# Main.net
KiCad netlist of a schematic drawn in EAGLE
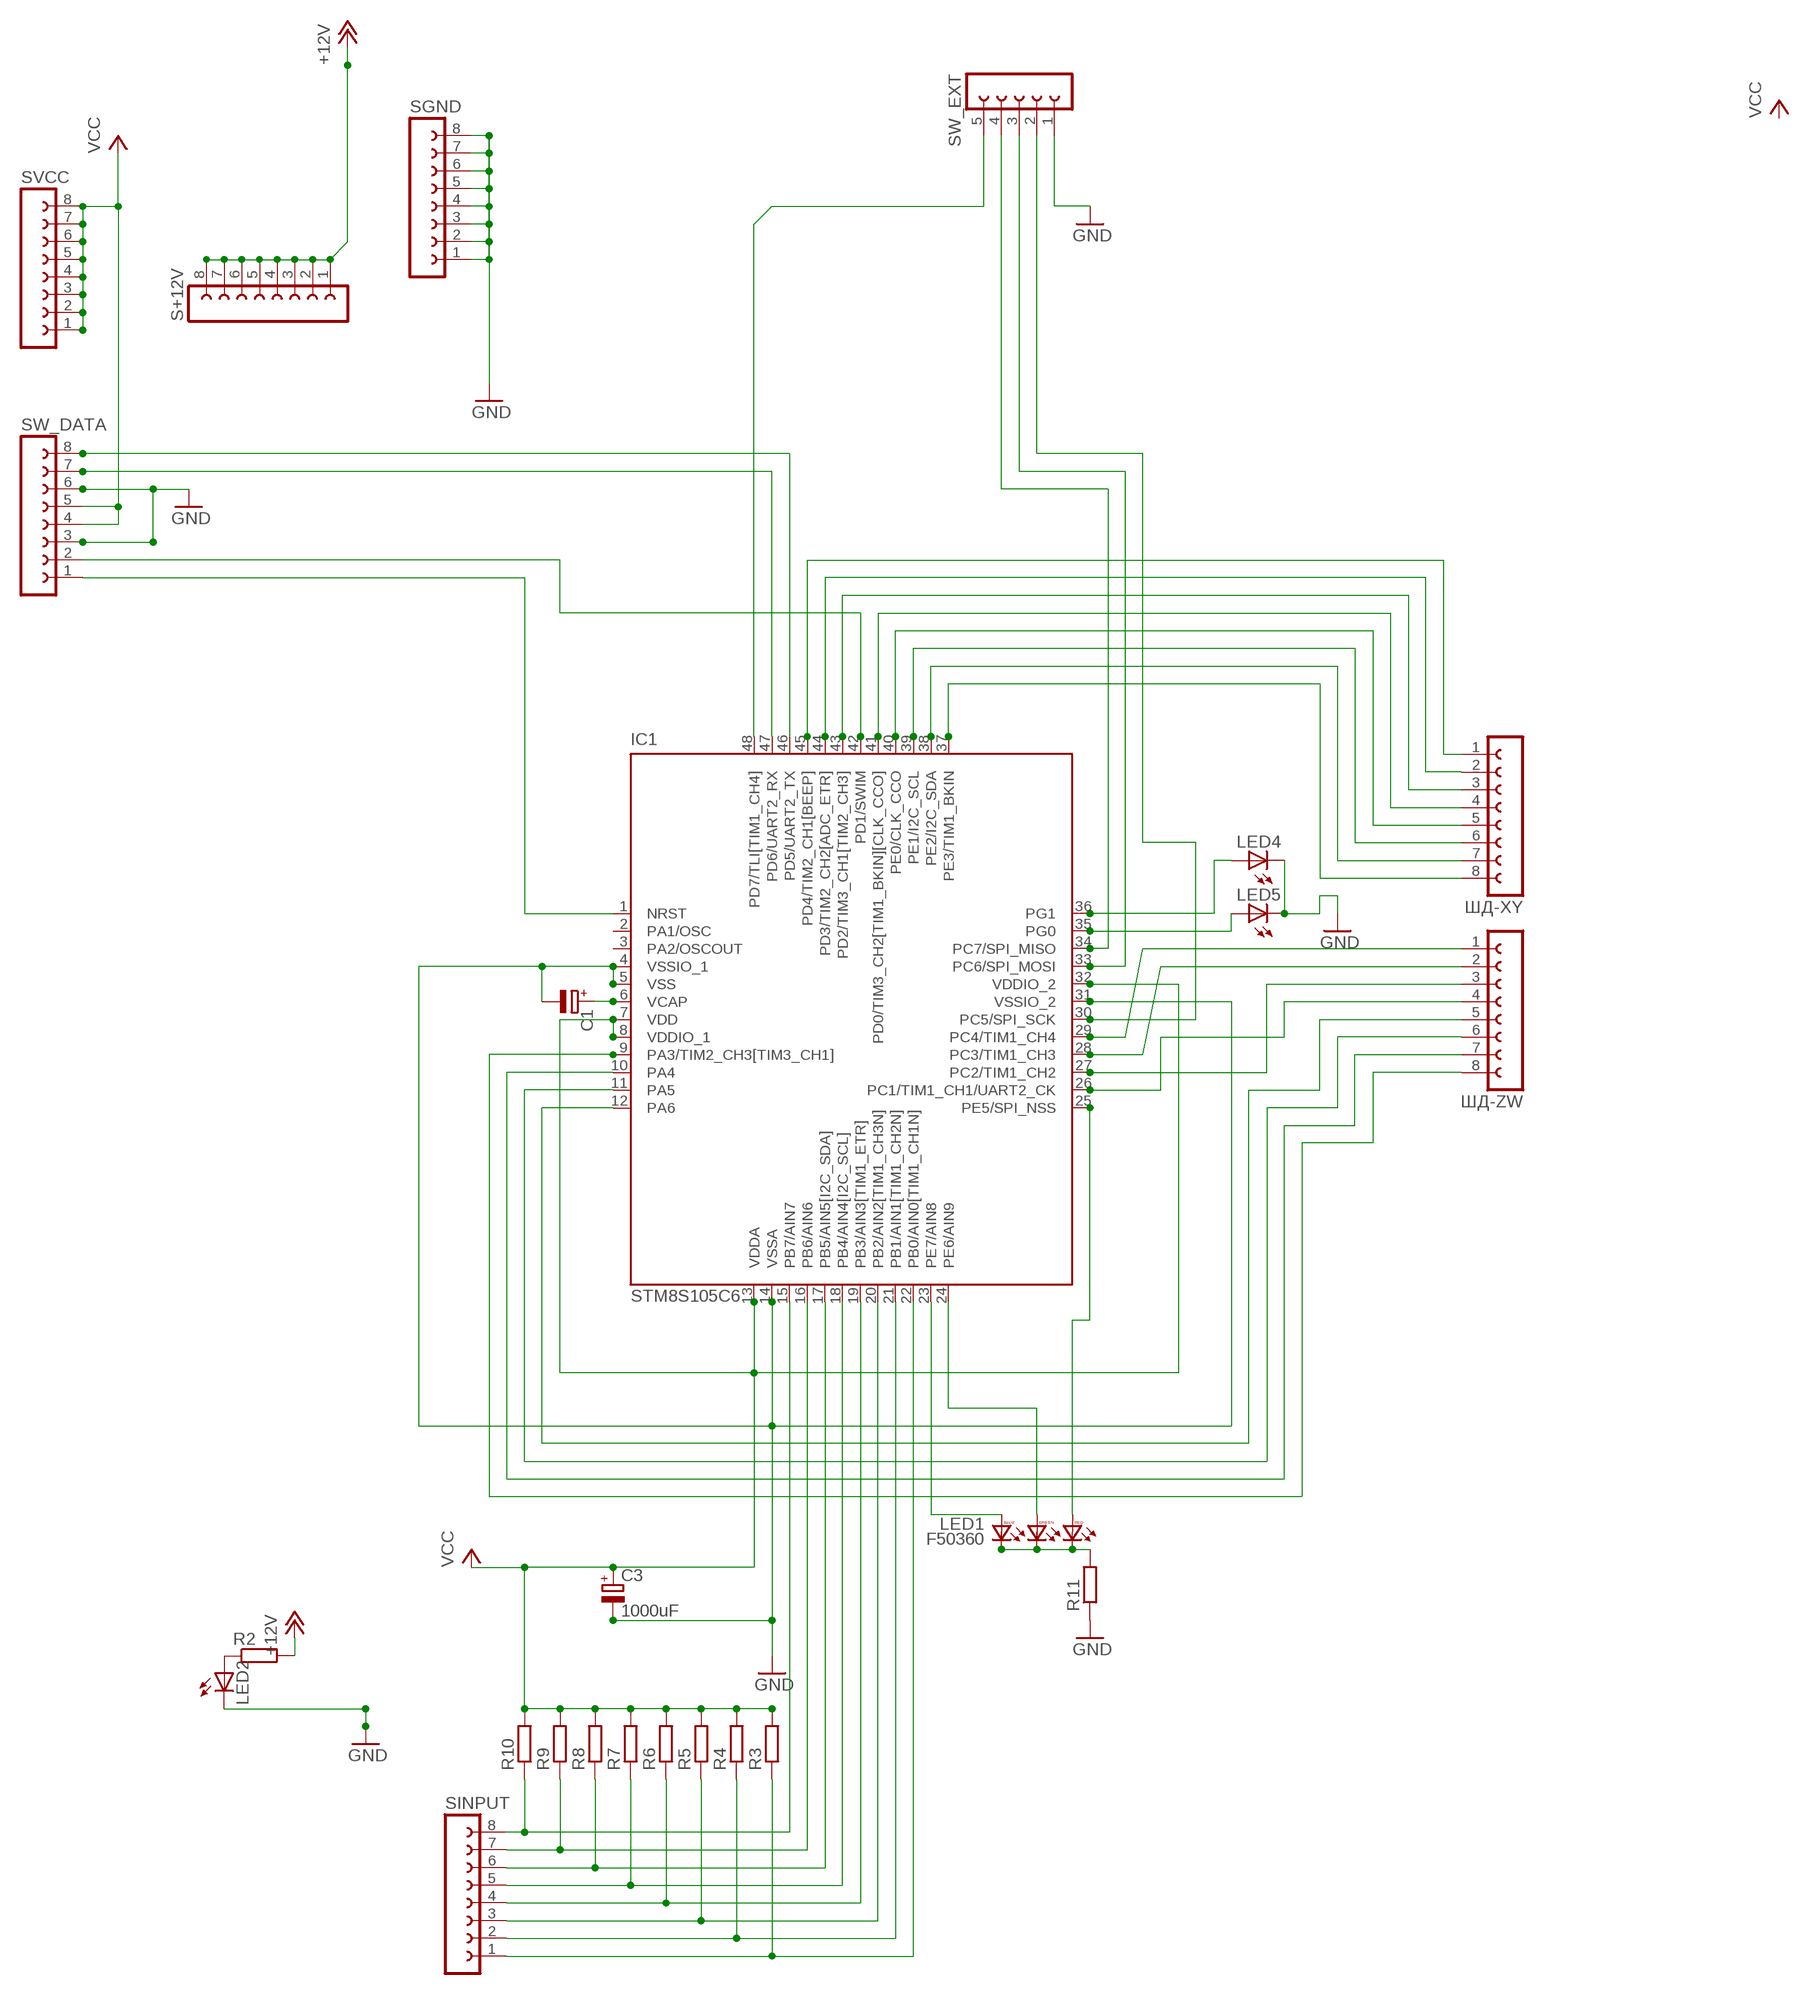
[diagram p0: schematic, sheet 1]

(export (version "E")
  (design (tool "Eeschema 10.0.6"))
  (components
    (comp (ref "C1")
      (value "CPOL-EUR/2012-12W")
      (footprint "eagle-import:R_2012-12W")
      (libsource (lib "eagle-import") (part "resistor_CPOL-EUR/2012-12W"))
    )
    (comp (ref "C3")
      (value "1000uF")
      (footprint "eagle-import:SANYO-OSCON_9E")
      (libsource (lib "eagle-import") (part "CPOL-EUSANYO_9E"))
    )
    (comp (ref "IC1")
      (value "STM8S105C6")
      (footprint "eagle-import:LQFP48-7X7")
      (fields (field (name "MPN") "STM8S105C6T6"))
      (libsource (lib "eagle-import") (part "STM8S105C6"))
    )
    (comp (ref "LED1")
      (value "F50360")
      (footprint "eagle-import:F50360")
      (libsource (lib "eagle-import") (part "F50360"))
    )
    (comp (ref "LED2")
      (value "LED3MM")
      (footprint "eagle-import:LED3MM")
      (libsource (lib "eagle-import") (part "LED3MM"))
    )
    (comp (ref "LED4")
      (value "LED3MM")
      (footprint "eagle-import:LED3MM")
      (libsource (lib "eagle-import") (part "LED3MM"))
    )
    (comp (ref "LED5")
      (value "LED3MM")
      (footprint "eagle-import:LED3MM")
      (libsource (lib "eagle-import") (part "LED3MM"))
    )
    (comp (ref "R2")
      (value "R-EU_0204/7")
      (footprint "eagle-import:0204_7")
      (libsource (lib "eagle-import") (part "R-EU_0204/7"))
    )
    (comp (ref "R3")
      (value "R-EU_M0805")
      (footprint "eagle-import:M0805")
      (libsource (lib "eagle-import") (part "R-EU_M0805"))
    )
    (comp (ref "R4")
      (value "R-EU_M0805")
      (footprint "eagle-import:M0805")
      (libsource (lib "eagle-import") (part "R-EU_M0805"))
    )
    (comp (ref "R5")
      (value "R-EU_M0805")
      (footprint "eagle-import:M0805")
      (libsource (lib "eagle-import") (part "R-EU_M0805"))
    )
    (comp (ref "R6")
      (value "R-EU_M0805")
      (footprint "eagle-import:M0805")
      (libsource (lib "eagle-import") (part "R-EU_M0805"))
    )
    (comp (ref "R7")
      (value "R-EU_M0805")
      (footprint "eagle-import:M0805")
      (libsource (lib "eagle-import") (part "R-EU_M0805"))
    )
    (comp (ref "R8")
      (value "R-EU_M0805")
      (footprint "eagle-import:M0805")
      (libsource (lib "eagle-import") (part "R-EU_M0805"))
    )
    (comp (ref "R9")
      (value "R-EU_M0805")
      (footprint "eagle-import:M0805")
      (libsource (lib "eagle-import") (part "R-EU_M0805"))
    )
    (comp (ref "R10")
      (value "R-EU_M0805")
      (footprint "eagle-import:M0805")
      (libsource (lib "eagle-import") (part "R-EU_M0805"))
    )
    (comp (ref "R11")
      (value "R-EU_0204/7")
      (footprint "eagle-import:0204_7")
      (libsource (lib "eagle-import") (part "R-EU_0204/7"))
    )
    (comp (ref "S+12V")
      (value "FE08-1")
      (footprint "eagle-import:FE08")
      (fields (field (name "OC_FARNELL") "unknown") (field (name "OC_NEWARK") "unknown"))
      (libsource (lib "eagle-import") (part "FE08-1"))
    )
    (comp (ref "SGND")
      (value "FE08-1")
      (footprint "eagle-import:FE08")
      (fields (field (name "OC_FARNELL") "unknown") (field (name "OC_NEWARK") "unknown"))
      (libsource (lib "eagle-import") (part "FE08-1"))
    )
    (comp (ref "SINPUT")
      (value "FE08-1")
      (footprint "eagle-import:FE08")
      (fields (field (name "OC_FARNELL") "unknown") (field (name "OC_NEWARK") "unknown"))
      (libsource (lib "eagle-import") (part "FE08-1"))
    )
    (comp (ref "SVCC")
      (value "FE08-1")
      (footprint "eagle-import:FE08")
      (fields (field (name "OC_FARNELL") "unknown") (field (name "OC_NEWARK") "unknown"))
      (libsource (lib "eagle-import") (part "FE08-1"))
    )
    (comp (ref "SW_DATA")
      (value "FE08-1")
      (footprint "eagle-import:FE08")
      (fields (field (name "OC_FARNELL") "unknown") (field (name "OC_NEWARK") "unknown"))
      (libsource (lib "eagle-import") (part "FE08-1"))
    )
    (comp (ref "SW_EXT")
      (value "FE05-1")
      (footprint "eagle-import:FE05-1")
      (libsource (lib "eagle-import") (part "FE05-1"))
    )
    (comp (ref "ШД-XY")
      (value "FE08-1")
      (footprint "eagle-import:FE08")
      (libsource (lib "eagle-import") (part "FE08-1"))
    )
    (comp (ref "ШД-ZW")
      (value "FE08-1")
      (footprint "eagle-import:FE08")
      (libsource (lib "eagle-import") (part "FE08-1"))
    )
  )
  (nets
    (net (code "1") (name "+12V") (class "Default")
      (node (ref "R2") (pin "2") (pinfunction "2_2") (pintype "passive"))
      (node (ref "S+12V") (pin "1") (pinfunction "1_1") (pintype "passive"))
      (node (ref "S+12V") (pin "2") (pinfunction "2_2") (pintype "passive"))
      (node (ref "S+12V") (pin "3") (pinfunction "3_3") (pintype "passive"))
      (node (ref "S+12V") (pin "4") (pinfunction "4_4") (pintype "passive"))
      (node (ref "S+12V") (pin "5") (pinfunction "5_5") (pintype "passive"))
      (node (ref "S+12V") (pin "6") (pinfunction "6_6") (pintype "passive"))
      (node (ref "S+12V") (pin "7") (pinfunction "7_7") (pintype "passive"))
      (node (ref "S+12V") (pin "8") (pinfunction "8_8") (pintype "passive"))
    )
    (net (code "2") (name "GND") (class "Default")
      (node (ref "C1") (pin "-") (pinfunction "-_-") (pintype "passive"))
      (node (ref "C3") (pin "-") (pinfunction "-_-") (pintype "passive"))
      (node (ref "IC1") (pin "14") (pinfunction "VSSA_14") (pintype "power_in"))
      (node (ref "IC1") (pin "31") (pinfunction "VSSIO_2_31") (pintype "power_in"))
      (node (ref "IC1") (pin "4") (pinfunction "VSSIO_1_4") (pintype "power_in"))
      (node (ref "IC1") (pin "5") (pinfunction "VSS_5") (pintype "power_in"))
      (node (ref "LED2") (pin "K") (pinfunction "C_K") (pintype "passive"))
      (node (ref "LED4") (pin "K") (pinfunction "C_K") (pintype "passive"))
      (node (ref "LED5") (pin "K") (pinfunction "C_K") (pintype "passive"))
      (node (ref "R11") (pin "1") (pinfunction "1_1") (pintype "passive"))
      (node (ref "SGND") (pin "1") (pinfunction "1_1") (pintype "passive"))
      (node (ref "SGND") (pin "2") (pinfunction "2_2") (pintype "passive"))
      (node (ref "SGND") (pin "3") (pinfunction "3_3") (pintype "passive"))
      (node (ref "SGND") (pin "4") (pinfunction "4_4") (pintype "passive"))
      (node (ref "SGND") (pin "5") (pinfunction "5_5") (pintype "passive"))
      (node (ref "SGND") (pin "6") (pinfunction "6_6") (pintype "passive"))
      (node (ref "SGND") (pin "7") (pinfunction "7_7") (pintype "passive"))
      (node (ref "SGND") (pin "8") (pinfunction "8_8") (pintype "passive"))
      (node (ref "SW_DATA") (pin "3") (pinfunction "3_3") (pintype "passive"))
      (node (ref "SW_DATA") (pin "6") (pinfunction "6_6") (pintype "passive"))
      (node (ref "SW_EXT") (pin "1") (pinfunction "1_1") (pintype "passive"))
    )
    (net (code "3") (name "Net-(IC1-NRST)") (class "Default")
      (node (ref "IC1") (pin "1") (pinfunction "NRST_1") (pintype "bidirectional"))
      (node (ref "SW_DATA") (pin "1") (pinfunction "1_1") (pintype "passive"))
    )
    (net (code "4") (name "Net-(IC1-PA3{slash}TIM2_CH3[TIM3_CH1])") (class "Default")
      (node (ref "IC1") (pin "9") (pinfunction "PA3/TIM2_CH3[TIM3_CH1]_9") (pintype "bidirectional"))
      (node (ref "ШД-ZW") (pin "8") (pinfunction "8_8") (pintype "passive"))
    )
    (net (code "5") (name "Net-(IC1-PA4)") (class "Default")
      (node (ref "IC1") (pin "10") (pinfunction "PA4_10") (pintype "bidirectional"))
      (node (ref "ШД-ZW") (pin "7") (pinfunction "7_7") (pintype "passive"))
    )
    (net (code "6") (name "Net-(IC1-PA5)") (class "Default")
      (node (ref "IC1") (pin "11") (pinfunction "PA5_11") (pintype "bidirectional"))
      (node (ref "ШД-ZW") (pin "6") (pinfunction "6_6") (pintype "passive"))
    )
    (net (code "7") (name "Net-(IC1-PA6)") (class "Default")
      (node (ref "IC1") (pin "12") (pinfunction "PA6_12") (pintype "bidirectional"))
      (node (ref "ШД-ZW") (pin "5") (pinfunction "5_5") (pintype "passive"))
    )
    (net (code "8") (name "Net-(IC1-PB0{slash}AIN0[TIM1_CH1N])") (class "Default")
      (node (ref "IC1") (pin "22") (pinfunction "PB0/AIN0[TIM1_CH1N]_22") (pintype "bidirectional"))
      (node (ref "R3") (pin "1") (pinfunction "1_1") (pintype "passive"))
      (node (ref "SINPUT") (pin "1") (pinfunction "1_1") (pintype "passive"))
    )
    (net (code "9") (name "Net-(IC1-PB1{slash}AIN1[TIM1_CH2N])") (class "Default")
      (node (ref "IC1") (pin "21") (pinfunction "PB1/AIN1[TIM1_CH2N]_21") (pintype "bidirectional"))
      (node (ref "R4") (pin "1") (pinfunction "1_1") (pintype "passive"))
      (node (ref "SINPUT") (pin "2") (pinfunction "2_2") (pintype "passive"))
    )
    (net (code "10") (name "Net-(IC1-PB2{slash}AIN2[TIM1_CH3N])") (class "Default")
      (node (ref "IC1") (pin "20") (pinfunction "PB2/AIN2[TIM1_CH3N]_20") (pintype "bidirectional"))
      (node (ref "R5") (pin "1") (pinfunction "1_1") (pintype "passive"))
      (node (ref "SINPUT") (pin "3") (pinfunction "3_3") (pintype "passive"))
    )
    (net (code "11") (name "Net-(IC1-PB3{slash}AIN3[TIM1_ETR])") (class "Default")
      (node (ref "IC1") (pin "19") (pinfunction "PB3/AIN3[TIM1_ETR]_19") (pintype "bidirectional"))
      (node (ref "R6") (pin "1") (pinfunction "1_1") (pintype "passive"))
      (node (ref "SINPUT") (pin "4") (pinfunction "4_4") (pintype "passive"))
    )
    (net (code "12") (name "Net-(IC1-PB4{slash}AIN4[I2C_SCL])") (class "Default")
      (node (ref "IC1") (pin "18") (pinfunction "PB4/AIN4[I2C_SCL]_18") (pintype "bidirectional"))
      (node (ref "R7") (pin "1") (pinfunction "1_1") (pintype "passive"))
      (node (ref "SINPUT") (pin "5") (pinfunction "5_5") (pintype "passive"))
    )
    (net (code "13") (name "Net-(IC1-PB5{slash}AIN5[I2C_SDA])") (class "Default")
      (node (ref "IC1") (pin "17") (pinfunction "PB5/AIN5[I2C_SDA]_17") (pintype "bidirectional"))
      (node (ref "R8") (pin "1") (pinfunction "1_1") (pintype "passive"))
      (node (ref "SINPUT") (pin "6") (pinfunction "6_6") (pintype "passive"))
    )
    (net (code "14") (name "Net-(IC1-PB6{slash}AIN6)") (class "Default")
      (node (ref "IC1") (pin "16") (pinfunction "PB6/AIN6_16") (pintype "bidirectional"))
      (node (ref "R9") (pin "1") (pinfunction "1_1") (pintype "passive"))
      (node (ref "SINPUT") (pin "7") (pinfunction "7_7") (pintype "passive"))
    )
    (net (code "15") (name "Net-(IC1-PB7{slash}AIN7)") (class "Default")
      (node (ref "IC1") (pin "15") (pinfunction "PB7/AIN7_15") (pintype "bidirectional"))
      (node (ref "R10") (pin "1") (pinfunction "1_1") (pintype "passive"))
      (node (ref "SINPUT") (pin "8") (pinfunction "8_8") (pintype "passive"))
    )
    (net (code "16") (name "Net-(IC1-PC1{slash}TIM1_CH1{slash}UART2_CK)") (class "Default")
      (node (ref "IC1") (pin "26") (pinfunction "PC1/TIM1_CH1/UART2_CK_26") (pintype "bidirectional"))
      (node (ref "ШД-ZW") (pin "4") (pinfunction "4_4") (pintype "passive"))
    )
    (net (code "17") (name "Net-(IC1-PC2{slash}TIM1_CH2)") (class "Default")
      (node (ref "IC1") (pin "27") (pinfunction "PC2/TIM1_CH2_27") (pintype "bidirectional"))
      (node (ref "ШД-ZW") (pin "3") (pinfunction "3_3") (pintype "passive"))
    )
    (net (code "18") (name "Net-(IC1-PC3{slash}TIM1_CH3)") (class "Default")
      (node (ref "IC1") (pin "28") (pinfunction "PC3/TIM1_CH3_28") (pintype "bidirectional"))
      (node (ref "ШД-ZW") (pin "2") (pinfunction "2_2") (pintype "passive"))
    )
    (net (code "19") (name "Net-(IC1-PC4{slash}TIM1_CH4)") (class "Default")
      (node (ref "IC1") (pin "29") (pinfunction "PC4/TIM1_CH4_29") (pintype "bidirectional"))
      (node (ref "ШД-ZW") (pin "1") (pinfunction "1_1") (pintype "passive"))
    )
    (net (code "20") (name "Net-(IC1-PC5{slash}SPI_SCK)") (class "Default")
      (node (ref "IC1") (pin "30") (pinfunction "PC5/SPI_SCK_30") (pintype "bidirectional"))
      (node (ref "SW_EXT") (pin "2") (pinfunction "2_2") (pintype "passive"))
    )
    (net (code "21") (name "Net-(IC1-PC6{slash}SPI_MOSI)") (class "Default")
      (node (ref "IC1") (pin "33") (pinfunction "PC6/SPI_MOSI_33") (pintype "bidirectional"))
      (node (ref "SW_EXT") (pin "3") (pinfunction "3_3") (pintype "passive"))
    )
    (net (code "22") (name "Net-(IC1-PC7{slash}SPI_MISO)") (class "Default")
      (node (ref "IC1") (pin "34") (pinfunction "PC7/SPI_MISO_34") (pintype "bidirectional"))
      (node (ref "SW_EXT") (pin "4") (pinfunction "4_4") (pintype "passive"))
    )
    (net (code "23") (name "Net-(IC1-PD0{slash}TIM3_CH2[TIM1_BKIN][CLK_CCO])") (class "Default")
      (node (ref "IC1") (pin "41") (pinfunction "PD0/TIM3_CH2[TIM1_BKIN][CLK_CCO]_41") (pintype "bidirectional"))
      (node (ref "ШД-XY") (pin "4") (pinfunction "4_4") (pintype "passive"))
    )
    (net (code "24") (name "Net-(IC1-PD1{slash}SWIM)") (class "Default")
      (node (ref "IC1") (pin "42") (pinfunction "PD1/SWIM_42") (pintype "bidirectional"))
      (node (ref "SW_DATA") (pin "2") (pinfunction "2_2") (pintype "passive"))
    )
    (net (code "25") (name "Net-(IC1-PD2{slash}TIM3_CH1[TIM2_CH3])") (class "Default")
      (node (ref "IC1") (pin "43") (pinfunction "PD2/TIM3_CH1[TIM2_CH3]_43") (pintype "bidirectional"))
      (node (ref "ШД-XY") (pin "3") (pinfunction "3_3") (pintype "passive"))
    )
    (net (code "26") (name "Net-(IC1-PD3{slash}TIM2_CH2[ADC_ETR])") (class "Default")
      (node (ref "IC1") (pin "44") (pinfunction "PD3/TIM2_CH2[ADC_ETR]_44") (pintype "bidirectional"))
      (node (ref "ШД-XY") (pin "2") (pinfunction "2_2") (pintype "passive"))
    )
    (net (code "27") (name "Net-(IC1-PD4{slash}TIM2_CH1[BEEP])") (class "Default")
      (node (ref "IC1") (pin "45") (pinfunction "PD4/TIM2_CH1[BEEP]_45") (pintype "bidirectional"))
      (node (ref "ШД-XY") (pin "1") (pinfunction "1_1") (pintype "passive"))
    )
    (net (code "28") (name "Net-(IC1-PD5{slash}UART2_TX)") (class "Default")
      (node (ref "IC1") (pin "46") (pinfunction "PD5/UART2_TX_46") (pintype "bidirectional"))
      (node (ref "SW_DATA") (pin "8") (pinfunction "8_8") (pintype "passive"))
    )
    (net (code "29") (name "Net-(IC1-PD6{slash}UART2_RX)") (class "Default")
      (node (ref "IC1") (pin "47") (pinfunction "PD6/UART2_RX_47") (pintype "bidirectional"))
      (node (ref "SW_DATA") (pin "7") (pinfunction "7_7") (pintype "passive"))
    )
    (net (code "30") (name "Net-(IC1-PD7{slash}TLI[TIM1_CH4])") (class "Default")
      (node (ref "IC1") (pin "48") (pinfunction "PD7/TLI[TIM1_CH4]_48") (pintype "bidirectional"))
      (node (ref "SW_EXT") (pin "5") (pinfunction "5_5") (pintype "passive"))
    )
    (net (code "31") (name "Net-(IC1-PE0{slash}CLK_CCO)") (class "Default")
      (node (ref "IC1") (pin "40") (pinfunction "PE0/CLK_CCO_40") (pintype "bidirectional"))
      (node (ref "ШД-XY") (pin "5") (pinfunction "5_5") (pintype "passive"))
    )
    (net (code "32") (name "Net-(IC1-PE1{slash}I2C_SCL)") (class "Default")
      (node (ref "IC1") (pin "39") (pinfunction "PE1/I2C_SCL_39") (pintype "bidirectional"))
      (node (ref "ШД-XY") (pin "6") (pinfunction "6_6") (pintype "passive"))
    )
    (net (code "33") (name "Net-(IC1-PE2{slash}I2C_SDA)") (class "Default")
      (node (ref "IC1") (pin "38") (pinfunction "PE2/I2C_SDA_38") (pintype "bidirectional"))
      (node (ref "ШД-XY") (pin "7") (pinfunction "7_7") (pintype "passive"))
    )
    (net (code "34") (name "Net-(IC1-PE3{slash}TIM1_BKIN)") (class "Default")
      (node (ref "IC1") (pin "37") (pinfunction "PE3/TIM1_BKIN_37") (pintype "bidirectional"))
      (node (ref "ШД-XY") (pin "8") (pinfunction "8_8") (pintype "passive"))
    )
    (net (code "35") (name "Net-(IC1-PE5{slash}SPI_NSS)") (class "Default")
      (node (ref "IC1") (pin "25") (pinfunction "PE5/SPI_NSS_25") (pintype "bidirectional"))
      (node (ref "LED1") (pin "RA") (pinfunction "RA_RA") (pintype "passive"))
    )
    (net (code "36") (name "Net-(IC1-PE6{slash}AIN9)") (class "Default")
      (node (ref "IC1") (pin "24") (pinfunction "PE6/AIN9_24") (pintype "bidirectional"))
      (node (ref "LED1") (pin "GA") (pinfunction "GA_GA") (pintype "passive"))
    )
    (net (code "37") (name "Net-(IC1-PE7{slash}AIN8)") (class "Default")
      (node (ref "IC1") (pin "23") (pinfunction "PE7/AIN8_23") (pintype "bidirectional"))
      (node (ref "LED1") (pin "BA") (pinfunction "BA_BA") (pintype "passive"))
    )
    (net (code "38") (name "Net-(IC1-PG0)") (class "Default")
      (node (ref "IC1") (pin "35") (pinfunction "PG0_35") (pintype "bidirectional"))
      (node (ref "LED5") (pin "A") (pinfunction "A_A") (pintype "passive"))
    )
    (net (code "39") (name "Net-(IC1-PG1)") (class "Default")
      (node (ref "IC1") (pin "36") (pinfunction "PG1_36") (pintype "bidirectional"))
      (node (ref "LED4") (pin "A") (pinfunction "A_A") (pintype "passive"))
    )
    (net (code "40") (name "Net-(IC1-VCAP)") (class "Default")
      (node (ref "C1") (pin "+") (pinfunction "+_+") (pintype "passive"))
      (node (ref "IC1") (pin "6") (pinfunction "VCAP_6") (pintype "power_in"))
    )
    (net (code "41") (name "Net-(LED1-PadBC)") (class "Default")
      (node (ref "LED1") (pin "BC") (pinfunction "BC_BC") (pintype "passive"))
      (node (ref "LED1") (pin "GC") (pinfunction "GC_GC") (pintype "passive"))
      (node (ref "LED1") (pin "RC") (pinfunction "RC_RC") (pintype "passive"))
      (node (ref "R11") (pin "2") (pinfunction "2_2") (pintype "passive"))
    )
    (net (code "42") (name "Net-(LED2-PadA)") (class "Default")
      (node (ref "LED2") (pin "A") (pinfunction "A_A") (pintype "passive"))
      (node (ref "R2") (pin "1") (pinfunction "1_1") (pintype "passive"))
    )
    (net (code "43") (name "VCC") (class "Default")
      (node (ref "C3") (pin "+") (pinfunction "+_+") (pintype "passive"))
      (node (ref "IC1") (pin "13") (pinfunction "VDDA_13") (pintype "power_in"))
      (node (ref "IC1") (pin "32") (pinfunction "VDDIO_2_32") (pintype "power_in"))
      (node (ref "IC1") (pin "7") (pinfunction "VDD_7") (pintype "power_in"))
      (node (ref "IC1") (pin "8") (pinfunction "VDDIO_1_8") (pintype "power_in"))
      (node (ref "R10") (pin "2") (pinfunction "2_2") (pintype "passive"))
      (node (ref "R3") (pin "2") (pinfunction "2_2") (pintype "passive"))
      (node (ref "R4") (pin "2") (pinfunction "2_2") (pintype "passive"))
      (node (ref "R5") (pin "2") (pinfunction "2_2") (pintype "passive"))
      (node (ref "R6") (pin "2") (pinfunction "2_2") (pintype "passive"))
      (node (ref "R7") (pin "2") (pinfunction "2_2") (pintype "passive"))
      (node (ref "R8") (pin "2") (pinfunction "2_2") (pintype "passive"))
      (node (ref "R9") (pin "2") (pinfunction "2_2") (pintype "passive"))
      (node (ref "SVCC") (pin "1") (pinfunction "1_1") (pintype "passive"))
      (node (ref "SVCC") (pin "2") (pinfunction "2_2") (pintype "passive"))
      (node (ref "SVCC") (pin "3") (pinfunction "3_3") (pintype "passive"))
      (node (ref "SVCC") (pin "4") (pinfunction "4_4") (pintype "passive"))
      (node (ref "SVCC") (pin "5") (pinfunction "5_5") (pintype "passive"))
      (node (ref "SVCC") (pin "6") (pinfunction "6_6") (pintype "passive"))
      (node (ref "SVCC") (pin "7") (pinfunction "7_7") (pintype "passive"))
      (node (ref "SVCC") (pin "8") (pinfunction "8_8") (pintype "passive"))
      (node (ref "SW_DATA") (pin "4") (pinfunction "4_4") (pintype "passive"))
      (node (ref "SW_DATA") (pin "5") (pinfunction "5_5") (pintype "passive"))
    )
    (net (code "44") (name "unconnected-(IC1-PA1{slash}OSC-Pad2)") (class "Default")
      (node (ref "IC1") (pin "2") (pinfunction "PA1/OSC_2") (pintype "bidirectional"))
    )
    (net (code "45") (name "unconnected-(IC1-PA2{slash}OSCOUT-Pad3)") (class "Default")
      (node (ref "IC1") (pin "3") (pinfunction "PA2/OSCOUT_3") (pintype "bidirectional"))
    )
  )
)
